# Version_1.net
KiCad netlist of a schematic drawn in EAGLE
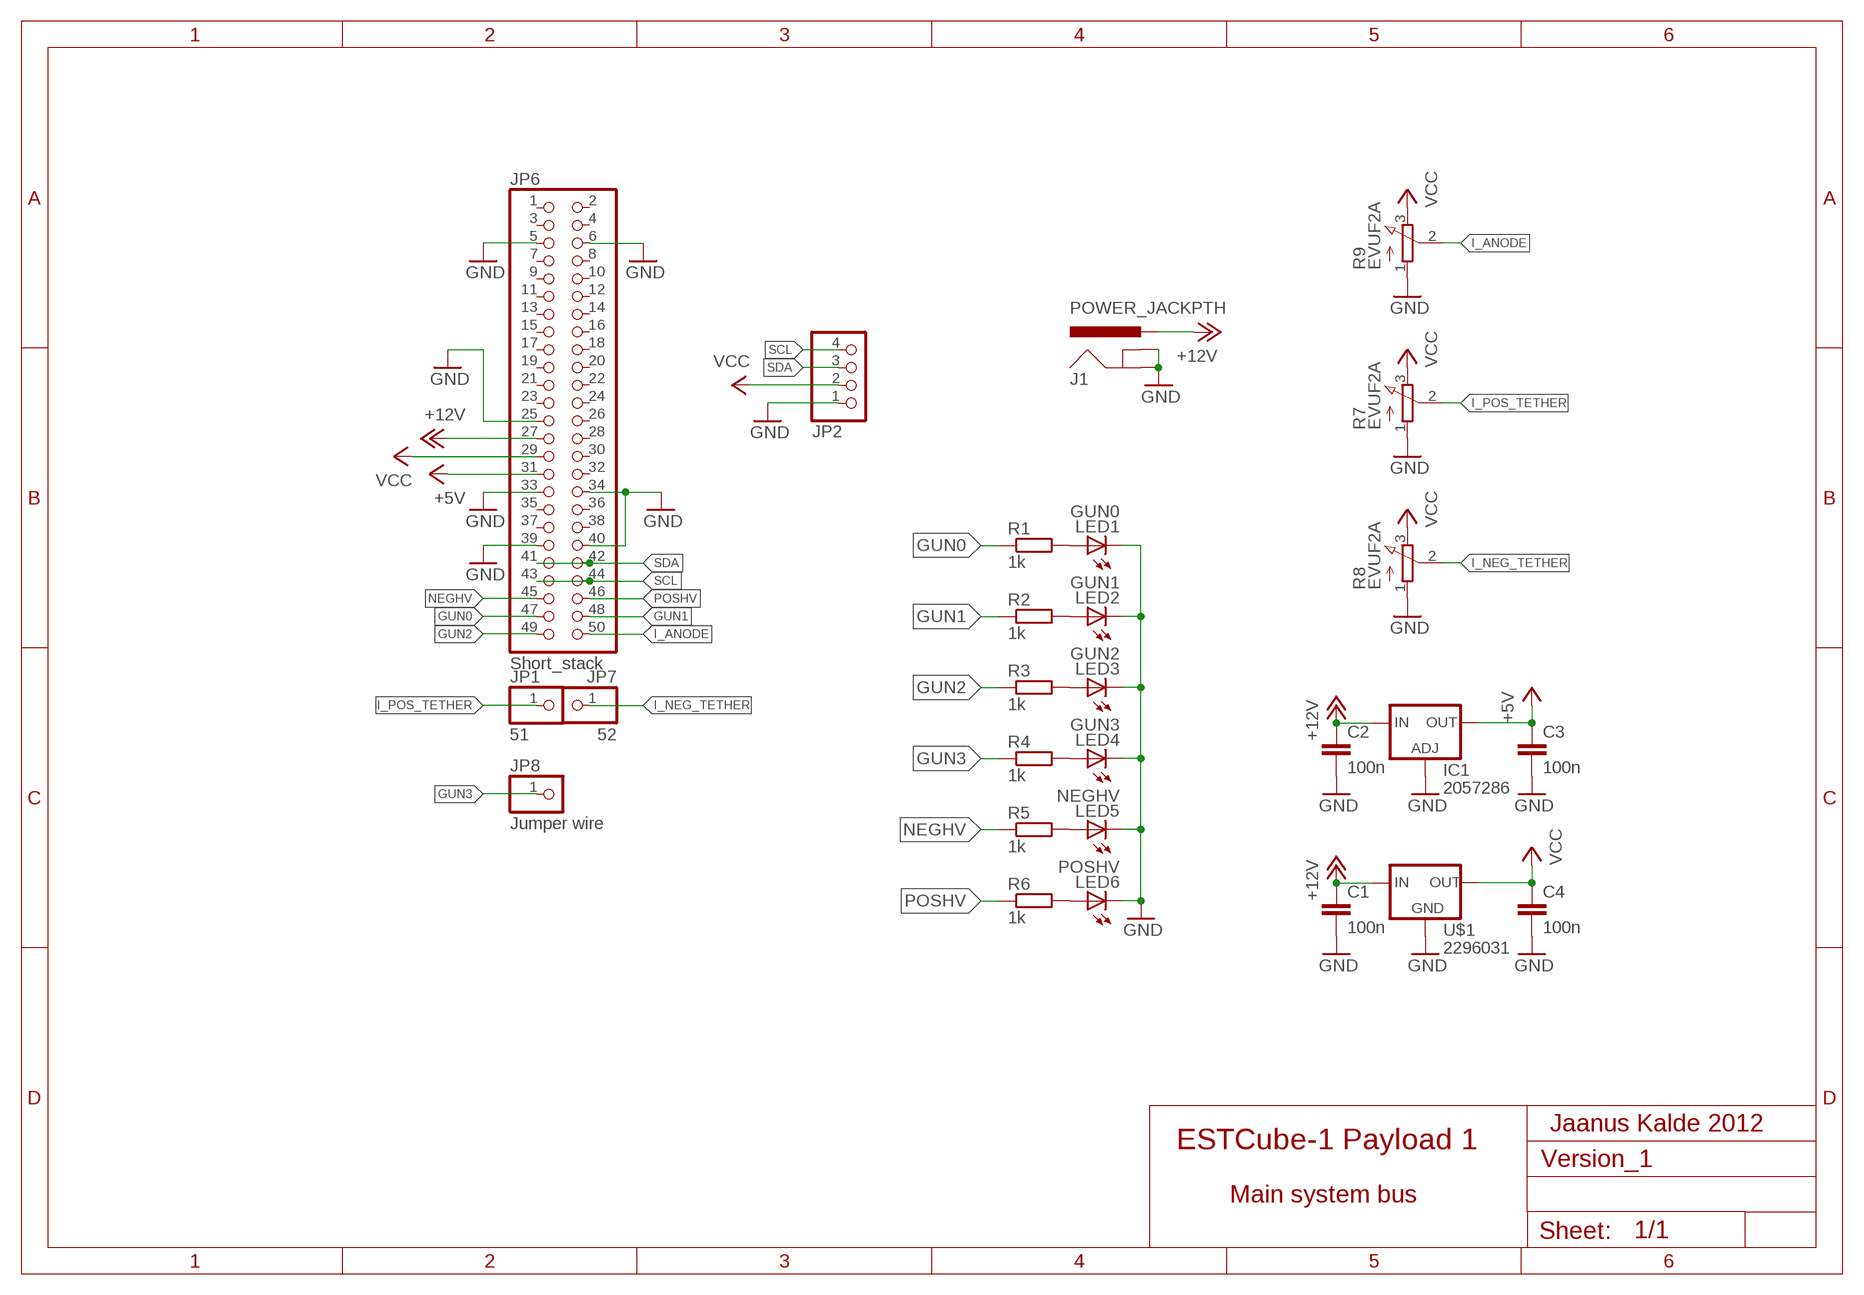
[diagram p0: schematic, sheet 1]

(export (version "E")
  (design (tool "Eeschema 10.0.6"))
  (components
    (comp (ref "C1")
      (value "100n")
      (footprint "eagle-import:C0603K")
      (libsource (lib "eagle-import") (part "C-EUC0603K"))
    )
    (comp (ref "C2")
      (value "100n")
      (footprint "eagle-import:C0603K")
      (libsource (lib "eagle-import") (part "C-EUC0603K"))
    )
    (comp (ref "C3")
      (value "100n")
      (footprint "eagle-import:C0603K")
      (libsource (lib "eagle-import") (part "C-EUC0603K"))
    )
    (comp (ref "C4")
      (value "100n")
      (footprint "eagle-import:C0603K")
      (libsource (lib "eagle-import") (part "C-EUC0603K"))
    )
    (comp (ref "IC1")
      (value "2057286")
      (footprint "eagle-import:SOT223")
      (libsource (lib "eagle-import") (part "LM317?MBSTT3"))
    )
    (comp (ref "J1")
      (value "POWER_JACKPTH")
      (footprint "eagle-import:POWER_JACK_PTH")
      (libsource (lib "eagle-import") (part "POWER_JACKPTH"))
    )
    (comp (ref "JP1")
      (value "51")
      (footprint "eagle-import:1X01")
      (libsource (lib "eagle-import") (part "PINHD-1X1"))
    )
    (comp (ref "JP2")
      (value "PINHD-1X4")
      (footprint "eagle-import:1X04")
      (libsource (lib "eagle-import") (part "PINHD-1X4"))
    )
    (comp (ref "JP6")
      (value "Short_stack")
      (footprint "eagle-import:2X25")
      (libsource (lib "eagle-import") (part "PINHD-2X25"))
    )
    (comp (ref "JP7")
      (value "52")
      (footprint "eagle-import:1X01")
      (libsource (lib "eagle-import") (part "PINHD-1X1"))
    )
    (comp (ref "JP8")
      (value "Jumper wire")
      (footprint "eagle-import:1X01")
      (libsource (lib "eagle-import") (part "PINHD-1X1"))
    )
    (comp (ref "LED1")
      (value "GUN0")
      (footprint "eagle-import:LED-0603")
      (libsource (lib "eagle-import") (part "LED0603"))
    )
    (comp (ref "LED2")
      (value "GUN1")
      (footprint "eagle-import:LED-0603")
      (libsource (lib "eagle-import") (part "LED0603"))
    )
    (comp (ref "LED3")
      (value "GUN2")
      (footprint "eagle-import:LED-0603")
      (libsource (lib "eagle-import") (part "LED0603"))
    )
    (comp (ref "LED4")
      (value "GUN3")
      (footprint "eagle-import:LED-0603")
      (libsource (lib "eagle-import") (part "LED0603"))
    )
    (comp (ref "LED5")
      (value "NEGHV")
      (footprint "eagle-import:LED-0603")
      (libsource (lib "eagle-import") (part "LED0603"))
    )
    (comp (ref "LED6")
      (value "POSHV")
      (footprint "eagle-import:LED-0603")
      (libsource (lib "eagle-import") (part "LED0603"))
    )
    (comp (ref "R1")
      (value "1k")
      (footprint "eagle-import:R0603")
      (libsource (lib "eagle-import") (part "R-EU_R0603"))
    )
    (comp (ref "R2")
      (value "1k")
      (footprint "eagle-import:R0603")
      (libsource (lib "eagle-import") (part "R-EU_R0603"))
    )
    (comp (ref "R3")
      (value "1k")
      (footprint "eagle-import:R0603")
      (libsource (lib "eagle-import") (part "R-EU_R0603"))
    )
    (comp (ref "R4")
      (value "1k")
      (footprint "eagle-import:R0603")
      (libsource (lib "eagle-import") (part "R-EU_R0603"))
    )
    (comp (ref "R5")
      (value "1k")
      (footprint "eagle-import:R0603")
      (libsource (lib "eagle-import") (part "R-EU_R0603"))
    )
    (comp (ref "R6")
      (value "1k")
      (footprint "eagle-import:R0603")
      (libsource (lib "eagle-import") (part "R-EU_R0603"))
    )
    (comp (ref "R7")
      (value "EVUF2A")
      (footprint "eagle-import:EVUF")
      (libsource (lib "eagle-import") (part "EVUAF2"))
    )
    (comp (ref "R8")
      (value "EVUF2A")
      (footprint "eagle-import:EVUF")
      (libsource (lib "eagle-import") (part "EVUAF2"))
    )
    (comp (ref "R9")
      (value "EVUF2A")
      (footprint "eagle-import:EVUF")
      (libsource (lib "eagle-import") (part "EVUAF2"))
    )
    (comp (ref "U$1")
      (value "2296031")
      (footprint "eagle-import:SOT223")
      (libsource (lib "eagle-import") (part "V_REG_MIC2920"))
    )
  )
  (nets
    (net (code "1") (name "+5V") (class "Default")
      (node (ref "C3") (pin "1") (pinfunction "1_1") (pintype "passive"))
      (node (ref "IC1") (pin "4") (pinfunction "OUT_4") (pintype "passive"))
      (node (ref "JP6") (pin "31") (pinfunction "31_31") (pintype "passive"))
    )
    (net (code "2") (name "+12V") (class "Default")
      (node (ref "C1") (pin "1") (pinfunction "1_1") (pintype "passive"))
      (node (ref "C2") (pin "1") (pinfunction "1_1") (pintype "passive"))
      (node (ref "IC1") (pin "3") (pinfunction "IN_3") (pintype "input"))
      (node (ref "J1") (pin "PWR") (pinfunction "PWR_PWR") (pintype "bidirectional"))
      (node (ref "JP6") (pin "27") (pinfunction "27_27") (pintype "passive"))
      (node (ref "U$1") (pin "1") (pinfunction "IN_1") (pintype "input"))
    )
    (net (code "3") (name "GND") (class "Default")
      (node (ref "C1") (pin "2") (pinfunction "2_2") (pintype "passive"))
      (node (ref "C2") (pin "2") (pinfunction "2_2") (pintype "passive"))
      (node (ref "C3") (pin "2") (pinfunction "2_2") (pintype "passive"))
      (node (ref "C4") (pin "2") (pinfunction "2_2") (pintype "passive"))
      (node (ref "IC1") (pin "1") (pinfunction "ADJ_1") (pintype "input"))
      (node (ref "J1") (pin "GND") (pinfunction "GND_GND") (pintype "bidirectional"))
      (node (ref "J1") (pin "GNDBREAK") (pinfunction "GNDBREAK_GNDBREAK") (pintype "bidirectional"))
      (node (ref "JP2") (pin "1") (pinfunction "1_1") (pintype "passive"))
      (node (ref "JP6") (pin "25") (pinfunction "25_25") (pintype "passive"))
      (node (ref "JP6") (pin "33") (pinfunction "33_33") (pintype "passive"))
      (node (ref "JP6") (pin "34") (pinfunction "34_34") (pintype "passive"))
      (node (ref "JP6") (pin "39") (pinfunction "39_39") (pintype "passive"))
      (node (ref "JP6") (pin "40") (pinfunction "40_40") (pintype "passive"))
      (node (ref "JP6") (pin "5") (pinfunction "5_5") (pintype "passive"))
      (node (ref "JP6") (pin "6") (pinfunction "6_6") (pintype "passive"))
      (node (ref "LED1") (pin "C") (pinfunction "C_C") (pintype "passive"))
      (node (ref "LED2") (pin "C") (pinfunction "C_C") (pintype "passive"))
      (node (ref "LED3") (pin "C") (pinfunction "C_C") (pintype "passive"))
      (node (ref "LED4") (pin "C") (pinfunction "C_C") (pintype "passive"))
      (node (ref "LED5") (pin "C") (pinfunction "C_C") (pintype "passive"))
      (node (ref "LED6") (pin "C") (pinfunction "C_C") (pintype "passive"))
      (node (ref "R7") (pin "1") (pinfunction "A_1") (pintype "passive"))
      (node (ref "R8") (pin "1") (pinfunction "A_1") (pintype "passive"))
      (node (ref "R9") (pin "1") (pinfunction "A_1") (pintype "passive"))
      (node (ref "U$1") (pin "2") (pinfunction "GND_2") (pintype "input"))
    )
    (net (code "4") (name "GUN0") (class "Default")
      (node (ref "JP6") (pin "47") (pinfunction "47_47") (pintype "passive"))
      (node (ref "R1") (pin "1") (pinfunction "1_1") (pintype "passive"))
    )
    (net (code "5") (name "GUN1") (class "Default")
      (node (ref "JP6") (pin "48") (pinfunction "48_48") (pintype "passive"))
      (node (ref "R2") (pin "1") (pinfunction "1_1") (pintype "passive"))
    )
    (net (code "6") (name "GUN2") (class "Default")
      (node (ref "JP6") (pin "49") (pinfunction "49_49") (pintype "passive"))
      (node (ref "R3") (pin "1") (pinfunction "1_1") (pintype "passive"))
    )
    (net (code "7") (name "GUN3") (class "Default")
      (node (ref "JP8") (pin "1") (pinfunction "1_1") (pintype "passive"))
      (node (ref "R4") (pin "1") (pinfunction "1_1") (pintype "passive"))
    )
    (net (code "8") (name "I_ANODE") (class "Default")
      (node (ref "JP6") (pin "50") (pinfunction "50_50") (pintype "passive"))
      (node (ref "R9") (pin "2") (pinfunction "S_2") (pintype "passive"))
    )
    (net (code "9") (name "I_NEG_TETHER") (class "Default")
      (node (ref "JP7") (pin "1") (pinfunction "1_1") (pintype "passive"))
      (node (ref "R8") (pin "2") (pinfunction "S_2") (pintype "passive"))
    )
    (net (code "10") (name "I_POS_TETHER") (class "Default")
      (node (ref "JP1") (pin "1") (pinfunction "1_1") (pintype "passive"))
      (node (ref "R7") (pin "2") (pinfunction "S_2") (pintype "passive"))
    )
    (net (code "11") (name "NEGHV") (class "Default")
      (node (ref "JP6") (pin "45") (pinfunction "45_45") (pintype "passive"))
      (node (ref "R5") (pin "1") (pinfunction "1_1") (pintype "passive"))
    )
    (net (code "12") (name "Net-(LED1-PadA)") (class "Default")
      (node (ref "LED1") (pin "A") (pinfunction "A_A") (pintype "passive"))
      (node (ref "R1") (pin "2") (pinfunction "2_2") (pintype "passive"))
    )
    (net (code "13") (name "Net-(LED2-PadA)") (class "Default")
      (node (ref "LED2") (pin "A") (pinfunction "A_A") (pintype "passive"))
      (node (ref "R2") (pin "2") (pinfunction "2_2") (pintype "passive"))
    )
    (net (code "14") (name "Net-(LED3-PadA)") (class "Default")
      (node (ref "LED3") (pin "A") (pinfunction "A_A") (pintype "passive"))
      (node (ref "R3") (pin "2") (pinfunction "2_2") (pintype "passive"))
    )
    (net (code "15") (name "Net-(LED4-PadA)") (class "Default")
      (node (ref "LED4") (pin "A") (pinfunction "A_A") (pintype "passive"))
      (node (ref "R4") (pin "2") (pinfunction "2_2") (pintype "passive"))
    )
    (net (code "16") (name "Net-(LED5-PadA)") (class "Default")
      (node (ref "LED5") (pin "A") (pinfunction "A_A") (pintype "passive"))
      (node (ref "R5") (pin "2") (pinfunction "2_2") (pintype "passive"))
    )
    (net (code "17") (name "Net-(LED6-PadA)") (class "Default")
      (node (ref "LED6") (pin "A") (pinfunction "A_A") (pintype "passive"))
      (node (ref "R6") (pin "2") (pinfunction "2_2") (pintype "passive"))
    )
    (net (code "18") (name "POSHV") (class "Default")
      (node (ref "JP6") (pin "46") (pinfunction "46_46") (pintype "passive"))
      (node (ref "R6") (pin "1") (pinfunction "1_1") (pintype "passive"))
    )
    (net (code "19") (name "SCL") (class "Default")
      (node (ref "JP2") (pin "4") (pinfunction "4_4") (pintype "passive"))
      (node (ref "JP6") (pin "43") (pinfunction "43_43") (pintype "passive"))
      (node (ref "JP6") (pin "44") (pinfunction "44_44") (pintype "passive"))
    )
    (net (code "20") (name "SDA") (class "Default")
      (node (ref "JP2") (pin "3") (pinfunction "3_3") (pintype "passive"))
      (node (ref "JP6") (pin "41") (pinfunction "41_41") (pintype "passive"))
      (node (ref "JP6") (pin "42") (pinfunction "42_42") (pintype "passive"))
    )
    (net (code "21") (name "VCC") (class "Default")
      (node (ref "C4") (pin "1") (pinfunction "1_1") (pintype "passive"))
      (node (ref "JP2") (pin "2") (pinfunction "2_2") (pintype "passive"))
      (node (ref "JP6") (pin "29") (pinfunction "29_29") (pintype "passive"))
      (node (ref "R7") (pin "3") (pinfunction "E_3") (pintype "passive"))
      (node (ref "R8") (pin "3") (pinfunction "E_3") (pintype "passive"))
      (node (ref "R9") (pin "3") (pinfunction "E_3") (pintype "passive"))
      (node (ref "U$1") (pin "3") (pinfunction "OUT_3") (pintype "output"))
    )
    (net (code "22") (name "unconnected-(JP6-Pad1)") (class "Default")
      (node (ref "JP6") (pin "1") (pinfunction "1_1") (pintype "passive"))
    )
    (net (code "23") (name "unconnected-(JP6-Pad2)") (class "Default")
      (node (ref "JP6") (pin "2") (pinfunction "2_2") (pintype "passive"))
    )
    (net (code "24") (name "unconnected-(JP6-Pad3)") (class "Default")
      (node (ref "JP6") (pin "3") (pinfunction "3_3") (pintype "passive"))
    )
    (net (code "25") (name "unconnected-(JP6-Pad4)") (class "Default")
      (node (ref "JP6") (pin "4") (pinfunction "4_4") (pintype "passive"))
    )
    (net (code "26") (name "unconnected-(JP6-Pad7)") (class "Default")
      (node (ref "JP6") (pin "7") (pinfunction "7_7") (pintype "passive"))
    )
    (net (code "27") (name "unconnected-(JP6-Pad8)") (class "Default")
      (node (ref "JP6") (pin "8") (pinfunction "8_8") (pintype "passive"))
    )
    (net (code "28") (name "unconnected-(JP6-Pad9)") (class "Default")
      (node (ref "JP6") (pin "9") (pinfunction "9_9") (pintype "passive"))
    )
    (net (code "29") (name "unconnected-(JP6-Pad10)") (class "Default")
      (node (ref "JP6") (pin "10") (pinfunction "10_10") (pintype "passive"))
    )
    (net (code "30") (name "unconnected-(JP6-Pad11)") (class "Default")
      (node (ref "JP6") (pin "11") (pinfunction "11_11") (pintype "passive"))
    )
    (net (code "31") (name "unconnected-(JP6-Pad12)") (class "Default")
      (node (ref "JP6") (pin "12") (pinfunction "12_12") (pintype "passive"))
    )
    (net (code "32") (name "unconnected-(JP6-Pad13)") (class "Default")
      (node (ref "JP6") (pin "13") (pinfunction "13_13") (pintype "passive"))
    )
    (net (code "33") (name "unconnected-(JP6-Pad14)") (class "Default")
      (node (ref "JP6") (pin "14") (pinfunction "14_14") (pintype "passive"))
    )
    (net (code "34") (name "unconnected-(JP6-Pad15)") (class "Default")
      (node (ref "JP6") (pin "15") (pinfunction "15_15") (pintype "passive"))
    )
    (net (code "35") (name "unconnected-(JP6-Pad16)") (class "Default")
      (node (ref "JP6") (pin "16") (pinfunction "16_16") (pintype "passive"))
    )
    (net (code "36") (name "unconnected-(JP6-Pad17)") (class "Default")
      (node (ref "JP6") (pin "17") (pinfunction "17_17") (pintype "passive"))
    )
    (net (code "37") (name "unconnected-(JP6-Pad18)") (class "Default")
      (node (ref "JP6") (pin "18") (pinfunction "18_18") (pintype "passive"))
    )
    (net (code "38") (name "unconnected-(JP6-Pad19)") (class "Default")
      (node (ref "JP6") (pin "19") (pinfunction "19_19") (pintype "passive"))
    )
    (net (code "39") (name "unconnected-(JP6-Pad20)") (class "Default")
      (node (ref "JP6") (pin "20") (pinfunction "20_20") (pintype "passive"))
    )
    (net (code "40") (name "unconnected-(JP6-Pad21)") (class "Default")
      (node (ref "JP6") (pin "21") (pinfunction "21_21") (pintype "passive"))
    )
    (net (code "41") (name "unconnected-(JP6-Pad22)") (class "Default")
      (node (ref "JP6") (pin "22") (pinfunction "22_22") (pintype "passive"))
    )
    (net (code "42") (name "unconnected-(JP6-Pad23)") (class "Default")
      (node (ref "JP6") (pin "23") (pinfunction "23_23") (pintype "passive"))
    )
    (net (code "43") (name "unconnected-(JP6-Pad24)") (class "Default")
      (node (ref "JP6") (pin "24") (pinfunction "24_24") (pintype "passive"))
    )
    (net (code "44") (name "unconnected-(JP6-Pad26)") (class "Default")
      (node (ref "JP6") (pin "26") (pinfunction "26_26") (pintype "passive"))
    )
    (net (code "45") (name "unconnected-(JP6-Pad28)") (class "Default")
      (node (ref "JP6") (pin "28") (pinfunction "28_28") (pintype "passive"))
    )
    (net (code "46") (name "unconnected-(JP6-Pad30)") (class "Default")
      (node (ref "JP6") (pin "30") (pinfunction "30_30") (pintype "passive"))
    )
    (net (code "47") (name "unconnected-(JP6-Pad32)") (class "Default")
      (node (ref "JP6") (pin "32") (pinfunction "32_32") (pintype "passive"))
    )
    (net (code "48") (name "unconnected-(JP6-Pad35)") (class "Default")
      (node (ref "JP6") (pin "35") (pinfunction "35_35") (pintype "passive"))
    )
    (net (code "49") (name "unconnected-(JP6-Pad36)") (class "Default")
      (node (ref "JP6") (pin "36") (pinfunction "36_36") (pintype "passive"))
    )
    (net (code "50") (name "unconnected-(JP6-Pad37)") (class "Default")
      (node (ref "JP6") (pin "37") (pinfunction "37_37") (pintype "passive"))
    )
    (net (code "51") (name "unconnected-(JP6-Pad38)") (class "Default")
      (node (ref "JP6") (pin "38") (pinfunction "38_38") (pintype "passive"))
    )
  )
)
